# MAIN.net
KiCad netlist of a schematic drawn in Altium Designer
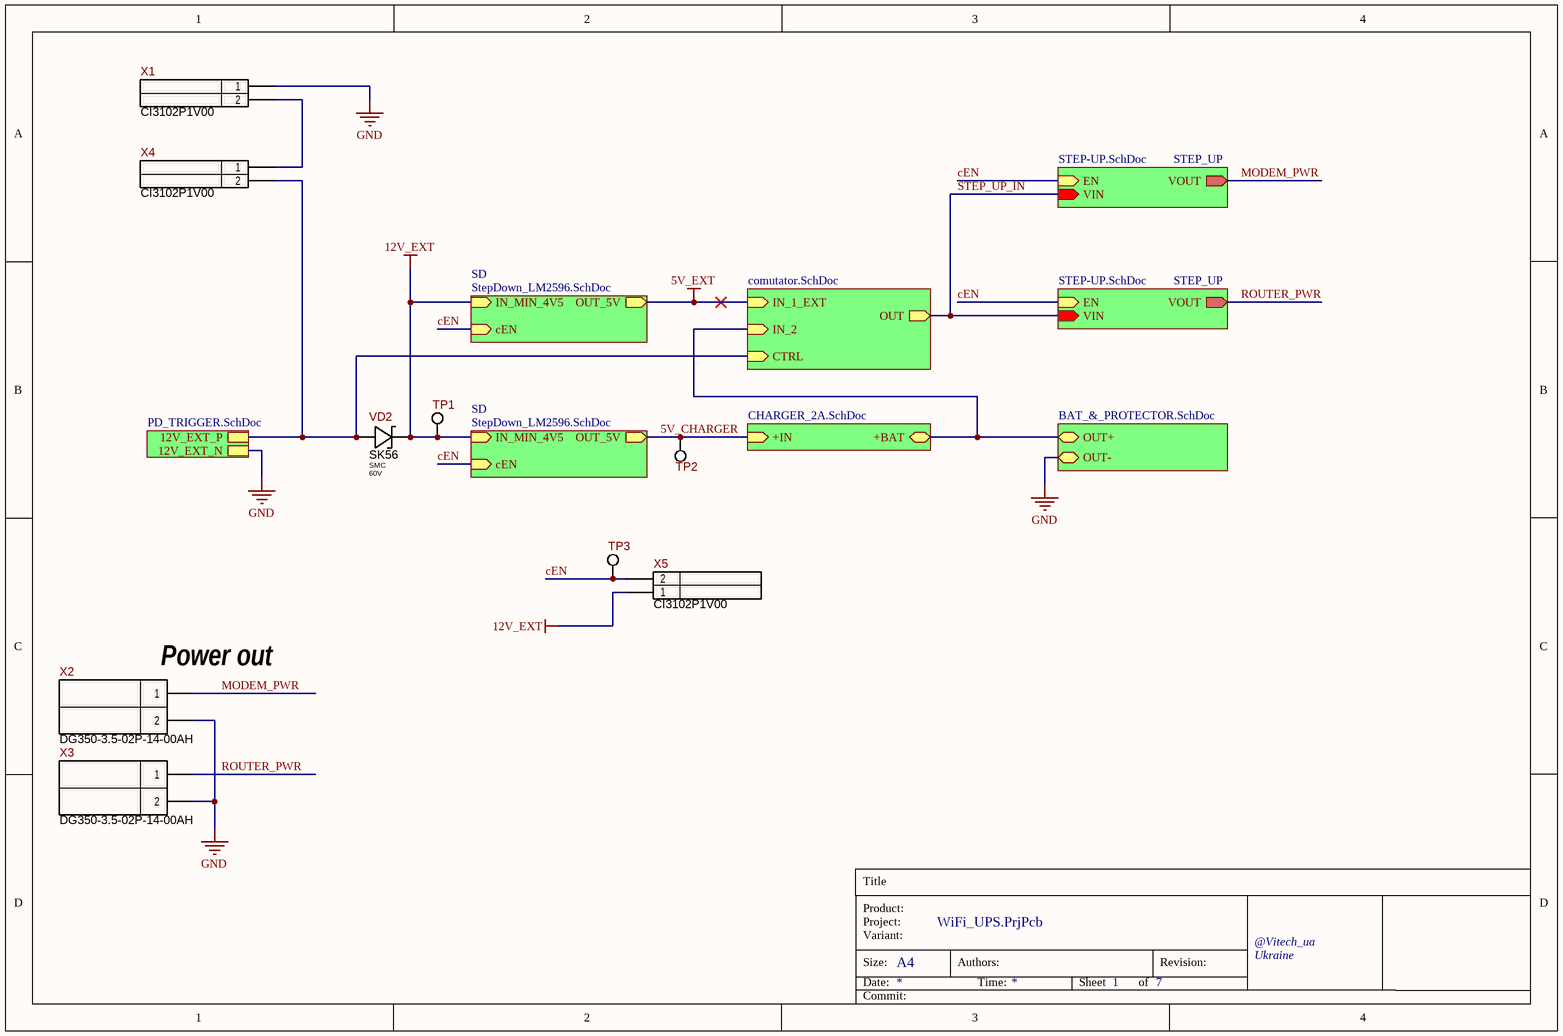
[diagram p0: MAIN.SchDoc]

(export (version "E")
  (design (tool "Eeschema 10.0.6"))
  (components
    (comp (ref "TP1")
      (value "PAD-0.96mm")
      (footprint "PAD-0.96mm")
      (description "0.96mm Pad for Plug-In or Receptacle")
      (fields (field (name "MANUFACTURER") "NONE"))
      (libsource (lib "probetools") (part "PAD-0.96mm"))
    )
    (comp (ref "TP2")
      (value "PAD-0.96mm")
      (footprint "PAD-0.96mm")
      (description "0.96mm Pad for Plug-In or Receptacle")
      (fields (field (name "MANUFACTURER") "NONE"))
      (libsource (lib "probetools") (part "PAD-0.96mm"))
    )
    (comp (ref "TP3")
      (value "PAD-0.96mm")
      (footprint "PAD-0.96mm")
      (description "0.96mm Pad for Plug-In or Receptacle")
      (fields (field (name "MANUFACTURER") "NONE"))
      (libsource (lib "probetools") (part "PAD-0.96mm"))
    )
    (comp (ref "VD2")
      (value "SK56")
      (footprint "SMC")
      (description "Diode Schottky 60V 5A, SMC")
      (fields
        (field (name "PART NUMBER") "SK56")
        (field (name "PACKAGE") "SMC")
        (field (name "VOLTAGE") "60V")
        (field (name "MANUFACTURER") "KLS")
      )
      (libsource (lib "vitech_semiconductors") (part "SS34"))
    )
    (comp (ref "X1")
      (value "WH-02S")
      (footprint "WF-2S")
      (description "WH Series 2.54mm Wire to Board Straight DIP Type Headers, 2 Pin")
      (fields (field (name "PART NUMBER") "CI3102P1V00") (field (name "MANUFACTURER") "CviLux"))
      (libsource (lib "vitech_connectors") (part "CI3102P1V00"))
    )
    (comp (ref "X2")
      (value "DG350-3.5-02P")
      (footprint "DG350-3.5-02P-14-00AH")
      (description "Screw Terminal, 3.5mm Pitch, 2 pin, Green")
      (fields (field (name "PART NUMBER") "DG350-3.5-02P-14-00AH") (field (name "MANUFACTURER") "Degson"))
      (libsource (lib "connectors") (part "DG350-3.5-02P-14-00AH"))
    )
    (comp (ref "X3")
      (value "DG350-3.5-02P")
      (footprint "DG350-3.5-02P-14-00AH")
      (description "Screw Terminal, 3.5mm Pitch, 2 pin, Green")
      (fields (field (name "PART NUMBER") "DG350-3.5-02P-14-00AH") (field (name "MANUFACTURER") "Degson"))
      (libsource (lib "connectors") (part "DG350-3.5-02P-14-00AH"))
    )
    (comp (ref "X4")
      (value "WH-02S")
      (footprint "WF-2S")
      (description "WH Series 2.54mm Wire to Board Straight DIP Type Headers, 2 Pin")
      (fields (field (name "PART NUMBER") "CI3102P1V00") (field (name "MANUFACTURER") "CviLux"))
      (libsource (lib "vitech_connectors") (part "CI3102P1V00"))
    )
    (comp (ref "X5")
      (value "WH-02S")
      (footprint "WF-2S")
      (description "WH Series 2.54mm Wire to Board Straight DIP Type Headers, 2 Pin")
      (fields (field (name "PART NUMBER") "CI3102P1V00") (field (name "MANUFACTURER") "CviLux"))
      (libsource (lib "") (part "CI3102P1V00_1"))
    )
  )
  (nets
    (net (code "2") (name "/5V_CHARGER") (class "Default") (node (ref "TP2") (pin "1") (pintype "passive")))
    (net (code "3") (name "/12V_EXT_P") (class "Default")
      (node (ref "VD2") (pin "AN") (pintype "passive"))
      (node (ref "X4") (pin "2") (pinfunction "2_2") (pintype "passive"))
    )
    (net (code "4") (name "/MODEM_PWR") (class "Default")
      (node (ref "X2") (pin "1") (pinfunction "1_1") (pintype "passive"))
    )
    (net (code "5") (name "/ROUTER_PWR") (class "Default")
      (node (ref "X3") (pin "1") (pinfunction "1_1") (pintype "passive"))
    )
    (net (code "7") (name "/cEN") (class "Default")
      (node (ref "TP3") (pin "1") (pintype "passive"))
      (node (ref "X5") (pin "2") (pinfunction "2_2") (pintype "passive"))
    )
    (net (code "9") (name "12V_EXT") (class "Default")
      (node (ref "TP1") (pin "1") (pintype "passive"))
      (node (ref "VD2") (pin "CA") (pintype "passive"))
      (node (ref "X5") (pin "1") (pinfunction "1_1") (pintype "passive"))
    )
    (net (code "10") (name "GND") (class "Default")
      (node (ref "X1") (pin "1") (pinfunction "1_1") (pintype "passive"))
      (node (ref "X2") (pin "2") (pinfunction "2_2") (pintype "passive"))
      (node (ref "X3") (pin "2") (pinfunction "2_2") (pintype "passive"))
    )
    (net (code "11") (name "Net-(X1-Pad2)") (class "Default")
      (node (ref "X1") (pin "2") (pinfunction "2_2") (pintype "passive"))
      (node (ref "X4") (pin "1") (pinfunction "1_1") (pintype "passive"))
    )
  )
)
